# mini-v1_10-smash.net
KiCad netlist of a schematic drawn in EAGLE
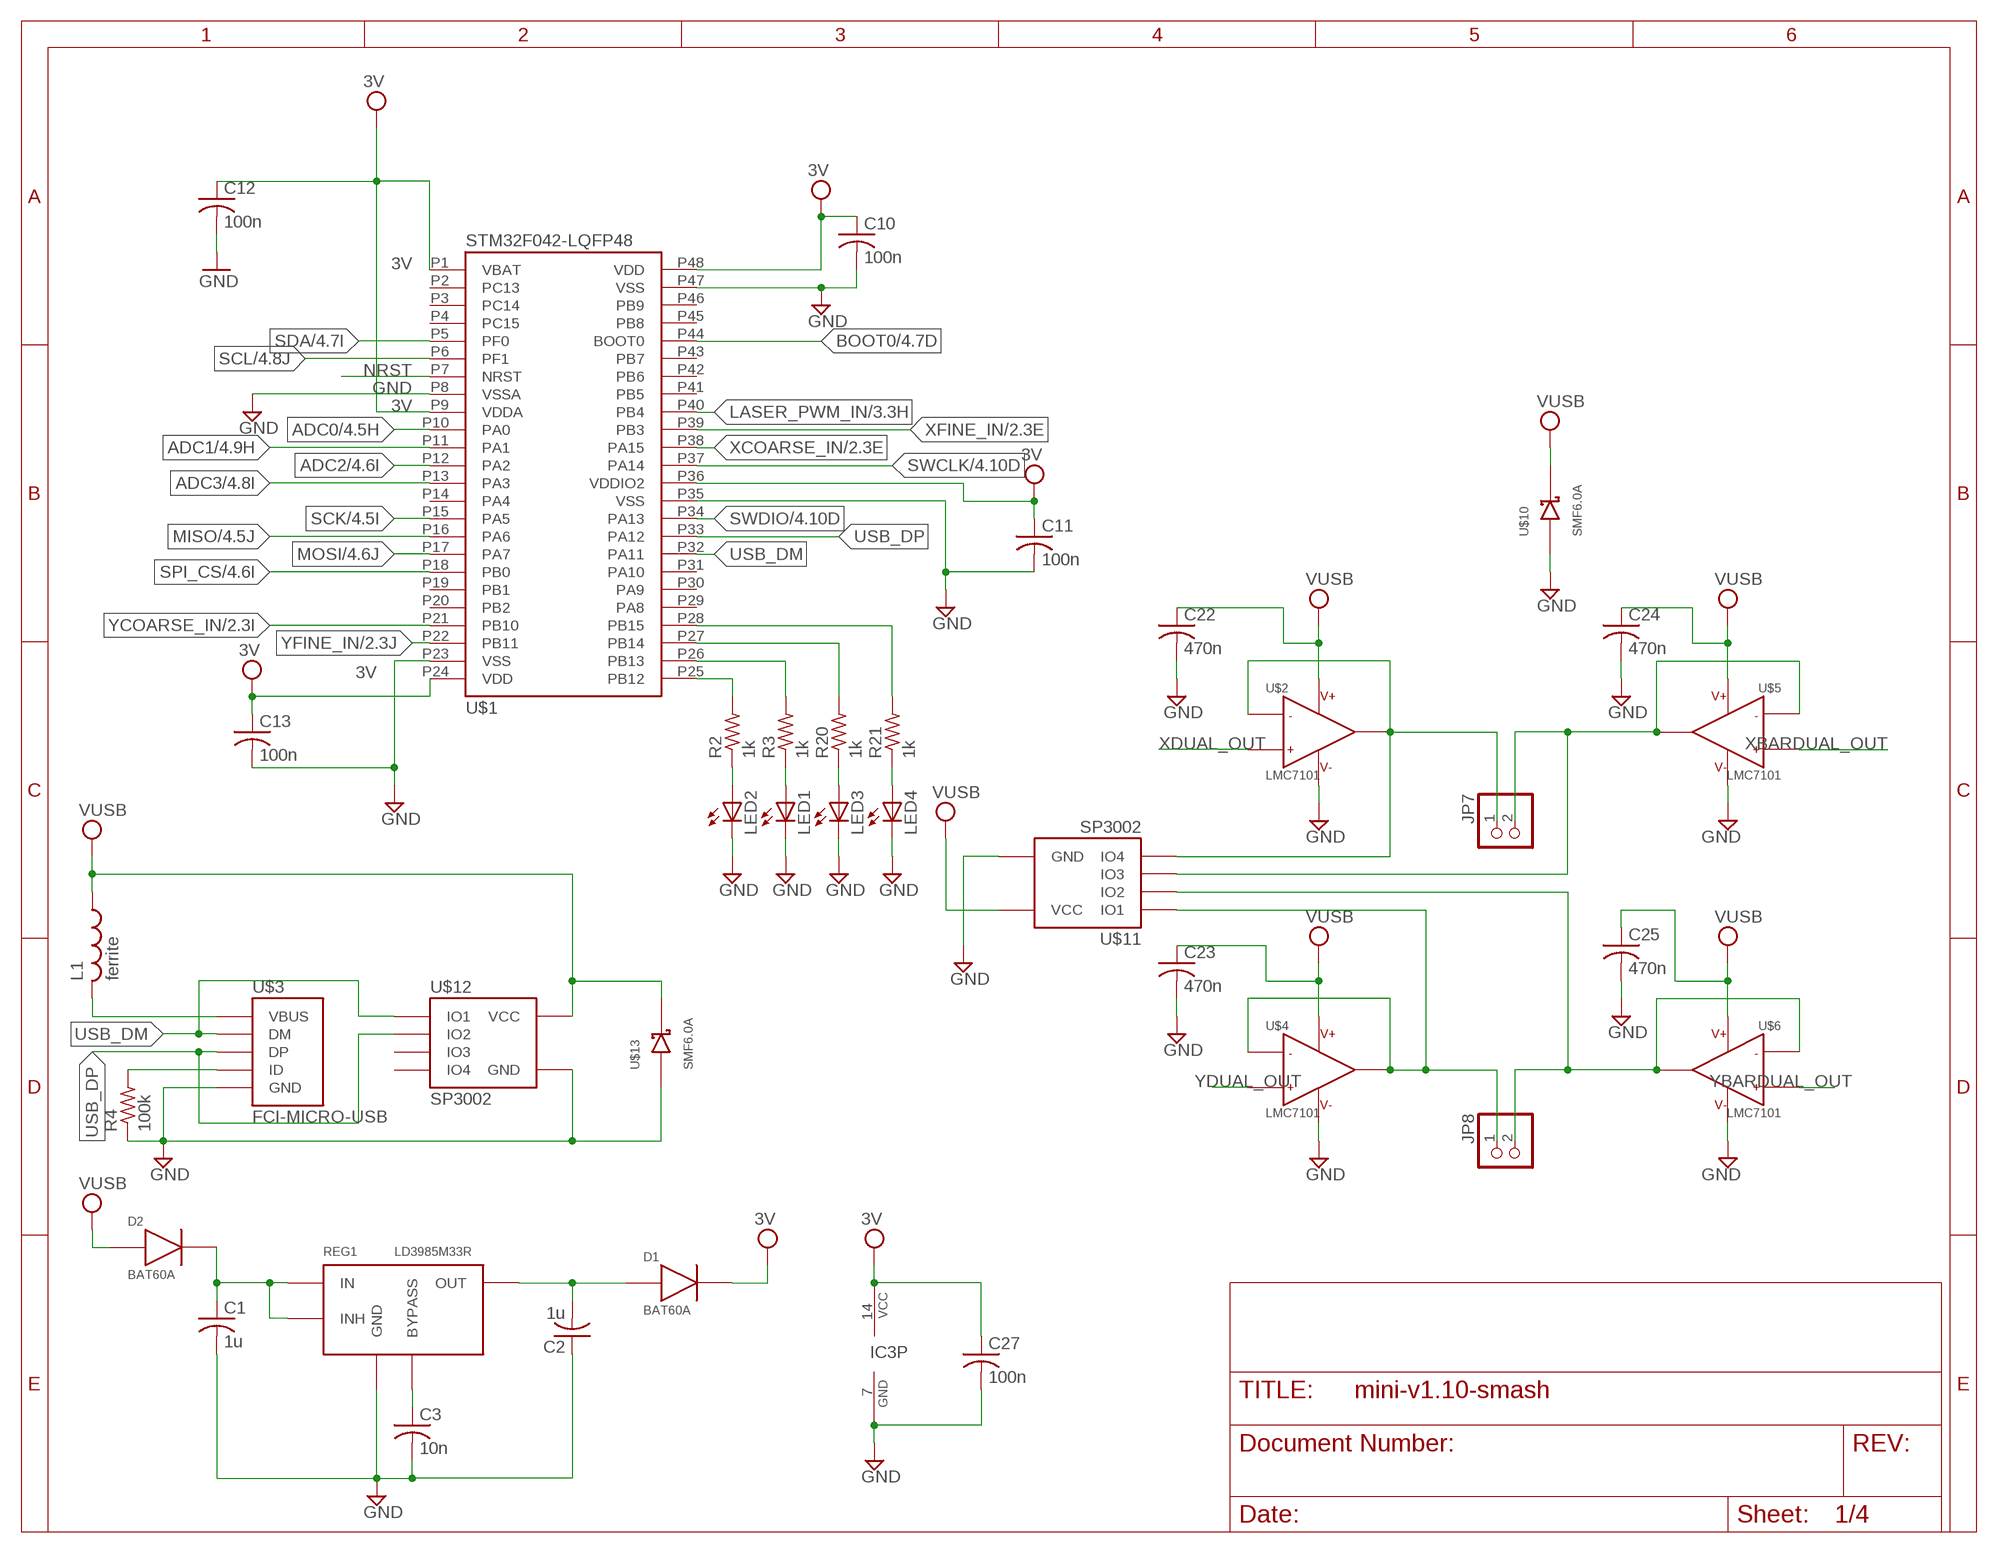
[diagram p0: schematic, sheet 1]
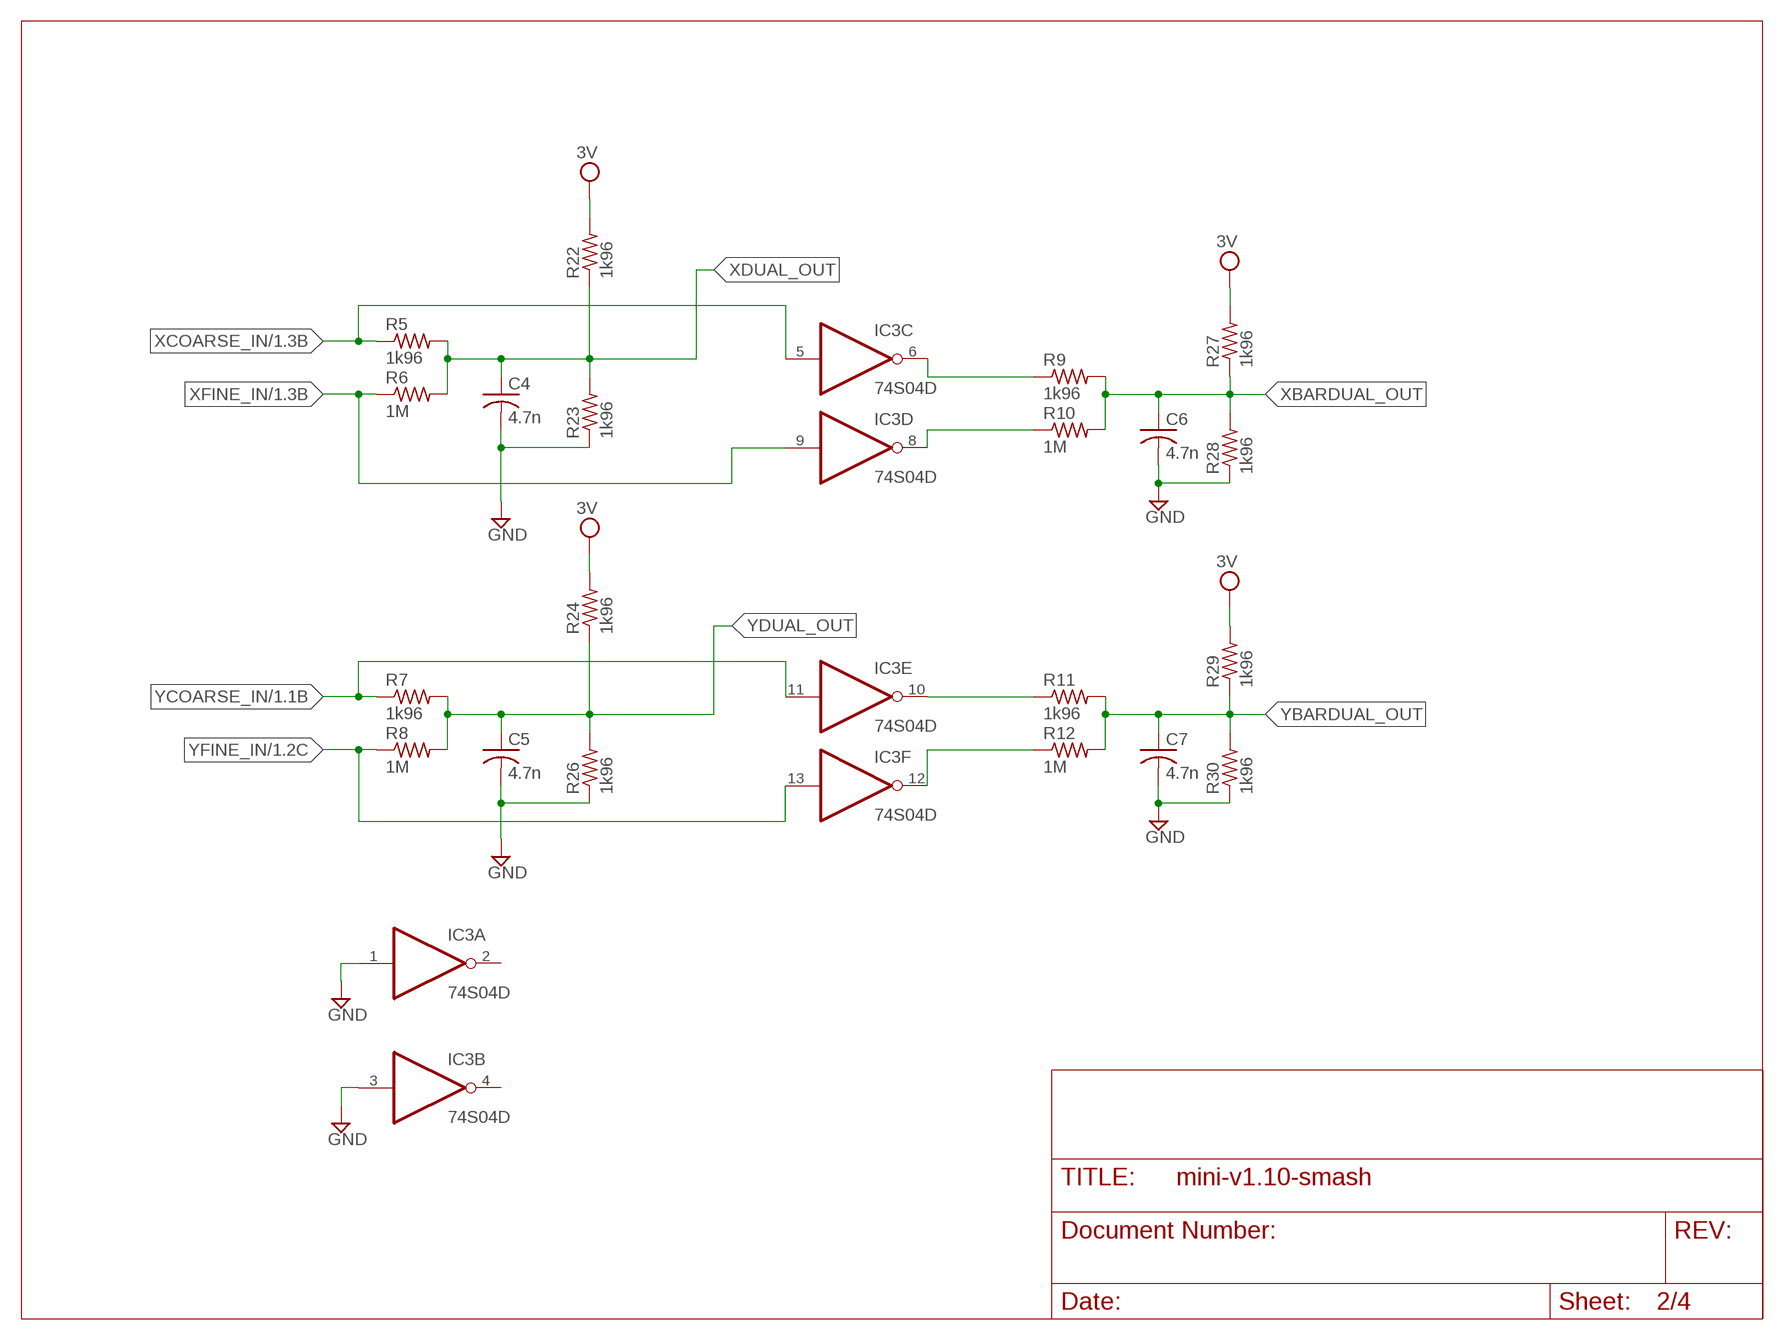
[diagram p1: schematic, sheet 2]
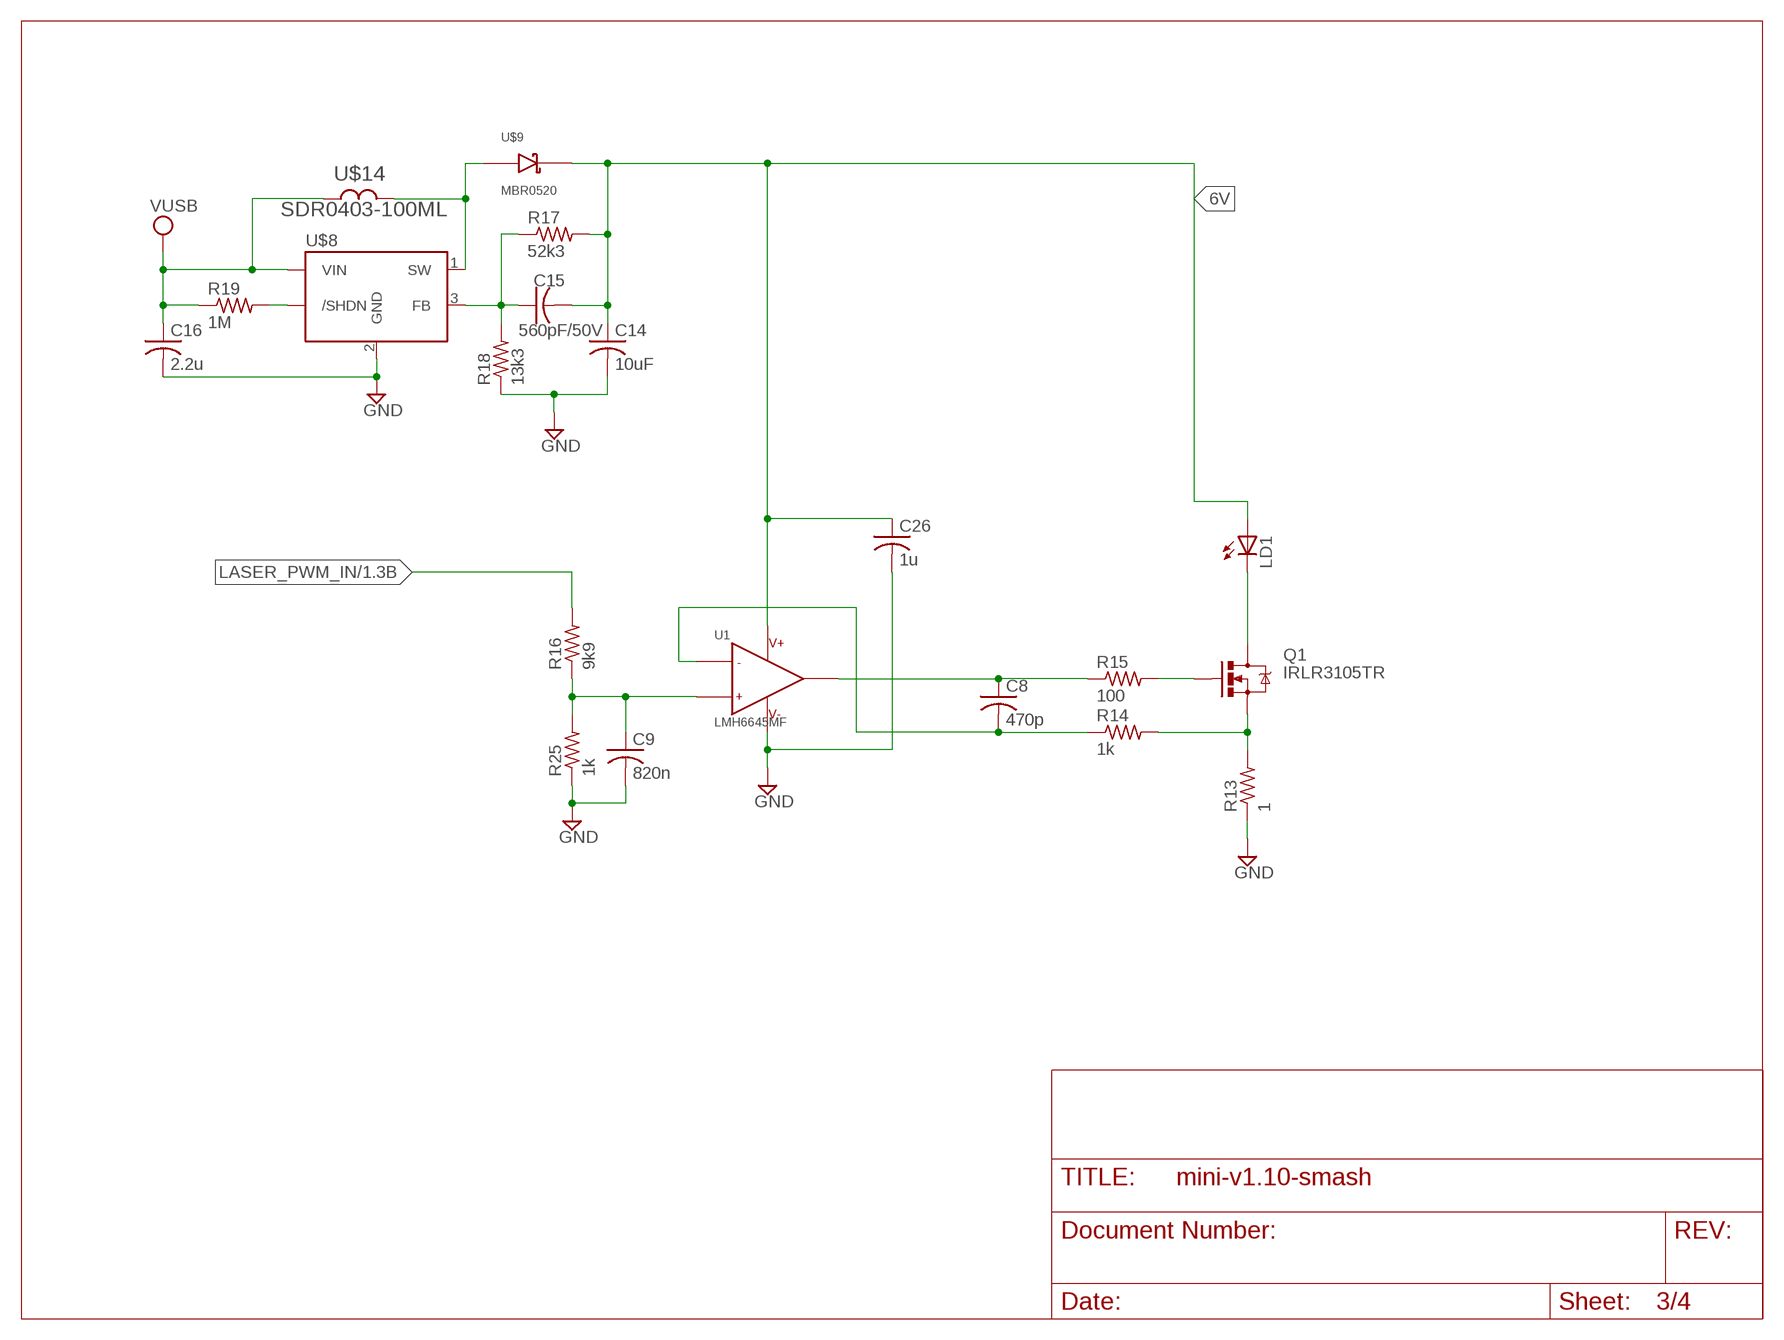
[diagram p2: schematic, sheet 3]
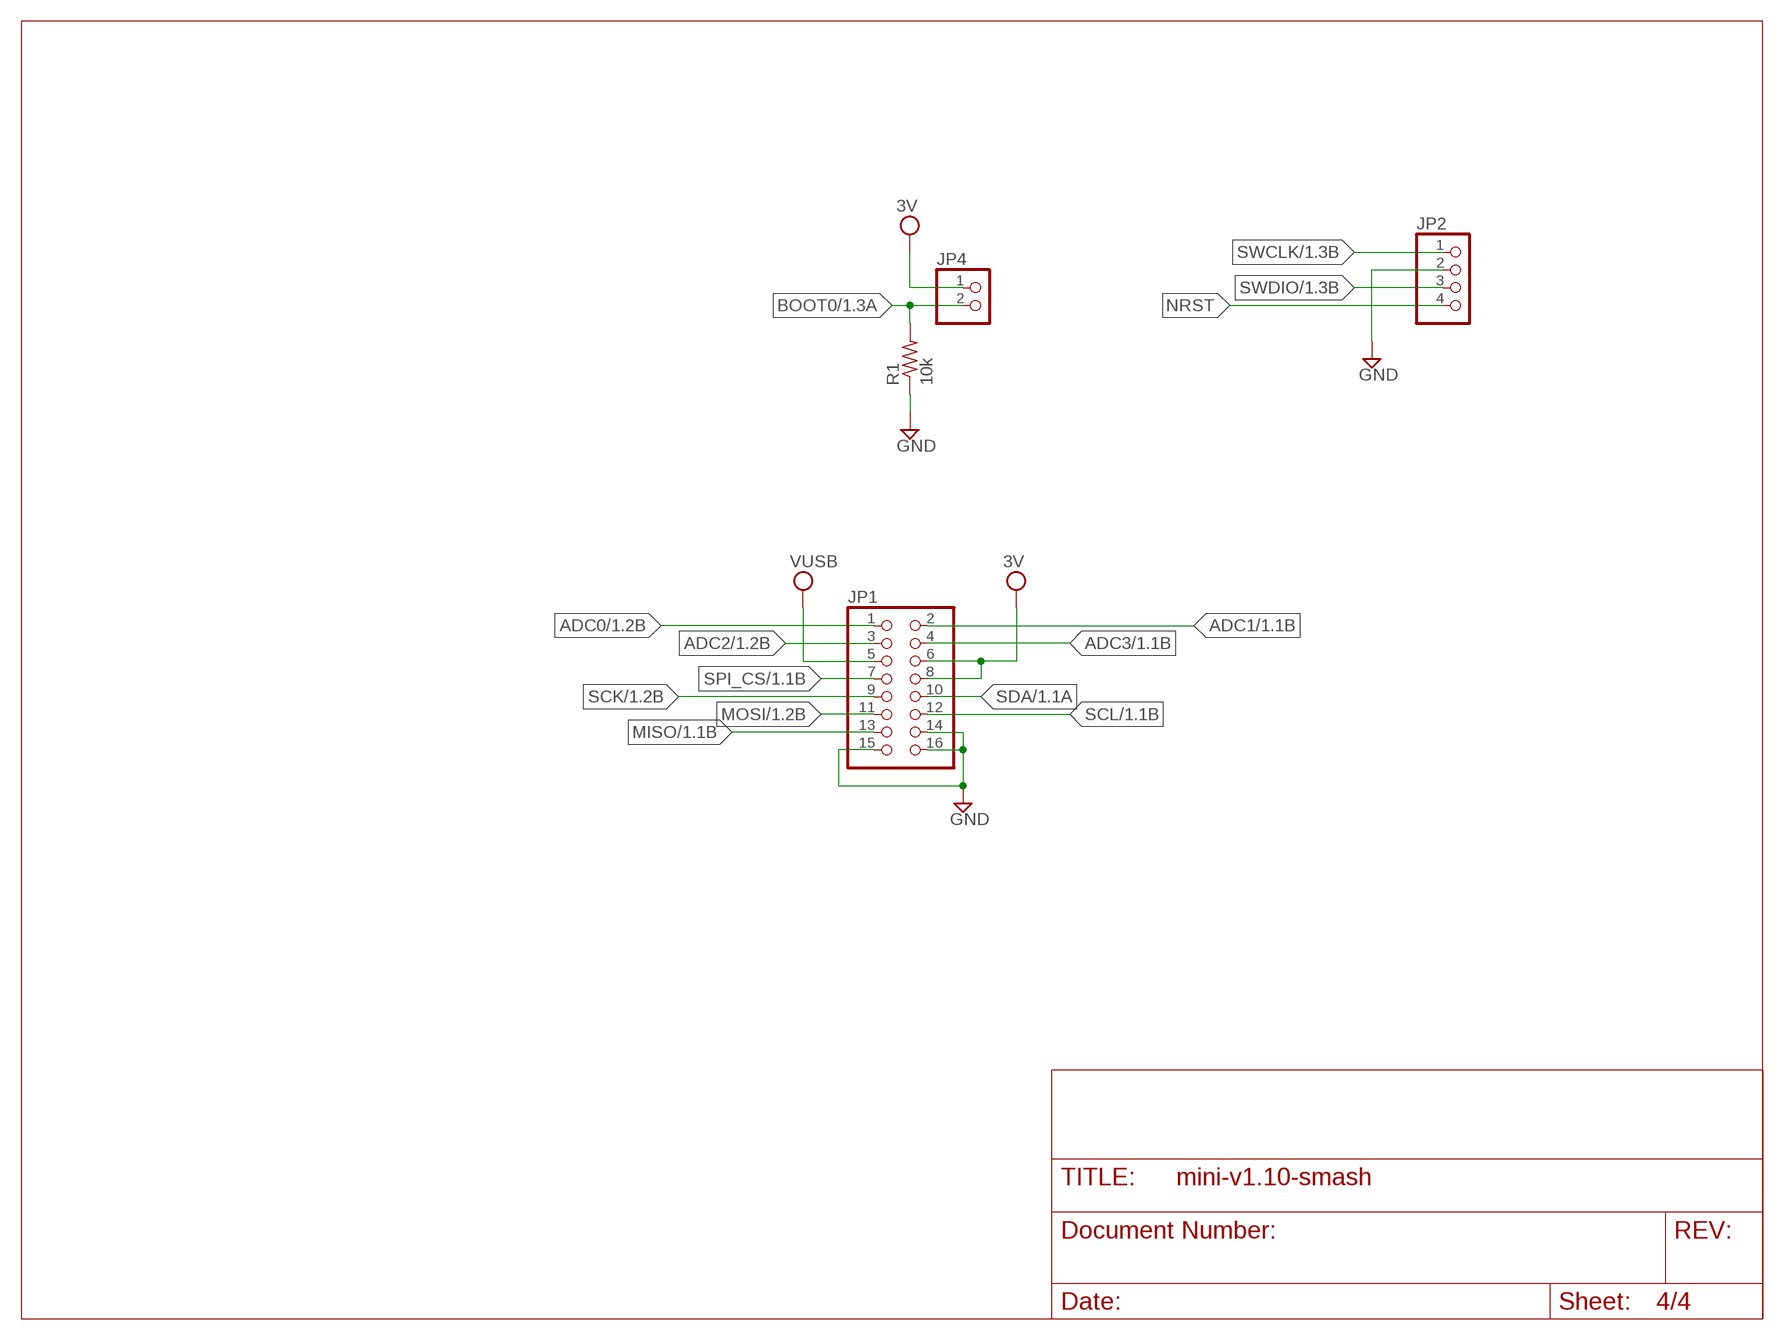
[diagram p3: schematic, sheet 4]

(export (version "E")
  (design (tool "Eeschema 10.0.6"))
  (components
    (comp (ref "C1")
      (value "1u")
      (footprint "eagle-import:C0603")
      (libsource (lib "eagle-import") (part "C-USC0603"))
    )
    (comp (ref "C2")
      (value "1u")
      (footprint "eagle-import:C0603")
      (libsource (lib "eagle-import") (part "C-USC0603"))
    )
    (comp (ref "C3")
      (value "10n")
      (footprint "eagle-import:C0603")
      (libsource (lib "eagle-import") (part "C-USC0603"))
    )
    (comp (ref "C10")
      (value "100n")
      (footprint "eagle-import:C0603")
      (libsource (lib "eagle-import") (part "C-USC0603"))
    )
    (comp (ref "C11")
      (value "100n")
      (footprint "eagle-import:C0603")
      (libsource (lib "eagle-import") (part "C-USC0603"))
    )
    (comp (ref "C12")
      (value "100n")
      (footprint "eagle-import:C0603")
      (libsource (lib "eagle-import") (part "C-USC0603"))
    )
    (comp (ref "C13")
      (value "100n")
      (footprint "eagle-import:C0603")
      (libsource (lib "eagle-import") (part "C-USC0603"))
    )
    (comp (ref "C22")
      (value "470n")
      (footprint "eagle-import:C0603")
      (libsource (lib "eagle-import") (part "C-USC0603"))
    )
    (comp (ref "C23")
      (value "470n")
      (footprint "eagle-import:C0603")
      (libsource (lib "eagle-import") (part "C-USC0603"))
    )
    (comp (ref "C24")
      (value "470n")
      (footprint "eagle-import:C0603")
      (libsource (lib "eagle-import") (part "C-USC0603"))
    )
    (comp (ref "C25")
      (value "470n")
      (footprint "eagle-import:C0603")
      (libsource (lib "eagle-import") (part "C-USC0603"))
    )
    (comp (ref "C27")
      (value "100n")
      (footprint "eagle-import:C0603")
      (libsource (lib "eagle-import") (part "C-USC0603"))
    )
    (comp (ref "D1")
      (value "BAT60A")
      (footprint "eagle-import:SOD323")
      (libsource (lib "eagle-import") (part "BAT60A"))
    )
    (comp (ref "D2")
      (value "BAT60A")
      (footprint "eagle-import:SOD323")
      (libsource (lib "eagle-import") (part "BAT60A"))
    )
    (comp (ref "IC3")
      (value "74S04D")
      (footprint "eagle-import:SO14")
      (libsource (lib "eagle-import") (part "7404DS"))
    )
    (comp (ref "JP7")
      (value "PINHD-1X2")
      (footprint "eagle-import:1X02")
      (libsource (lib "eagle-import") (part "PINHD-1X2"))
    )
    (comp (ref "JP8")
      (value "PINHD-1X2")
      (footprint "eagle-import:1X02")
      (libsource (lib "eagle-import") (part "PINHD-1X2"))
    )
    (comp (ref "L1")
      (value "ferrite")
      (footprint "eagle-import:C0603")
      (libsource (lib "eagle-import") (part "L-US"))
    )
    (comp (ref "LED1")
      (value "LEDCHIP-LED0603")
      (footprint "eagle-import:CHIP-LED0603")
      (libsource (lib "eagle-import") (part "LEDCHIP-LED0603"))
    )
    (comp (ref "LED2")
      (value "LEDCHIP-LED0603")
      (footprint "eagle-import:CHIP-LED0603")
      (libsource (lib "eagle-import") (part "LEDCHIP-LED0603"))
    )
    (comp (ref "LED3")
      (value "LEDCHIP-LED0603")
      (footprint "eagle-import:CHIP-LED0603")
      (libsource (lib "eagle-import") (part "LEDCHIP-LED0603"))
    )
    (comp (ref "LED4")
      (value "LEDCHIP-LED0603")
      (footprint "eagle-import:CHIP-LED0603")
      (libsource (lib "eagle-import") (part "LEDCHIP-LED0603"))
    )
    (comp (ref "R2")
      (value "1k")
      (footprint "eagle-import:R0603")
      (libsource (lib "eagle-import") (part "R-US_R0603"))
    )
    (comp (ref "R3")
      (value "1k")
      (footprint "eagle-import:R0603")
      (libsource (lib "eagle-import") (part "R-US_R0603"))
    )
    (comp (ref "R4")
      (value "100k")
      (footprint "eagle-import:R0603")
      (libsource (lib "eagle-import") (part "R-US_R0603"))
    )
    (comp (ref "R20")
      (value "1k")
      (footprint "eagle-import:R0603")
      (libsource (lib "eagle-import") (part "R-US_R0603"))
    )
    (comp (ref "R21")
      (value "1k")
      (footprint "eagle-import:R0603")
      (libsource (lib "eagle-import") (part "R-US_R0603"))
    )
    (comp (ref "REG1")
      (value "LD3985M33R")
      (footprint "eagle-import:SOT23-5L")
      (libsource (lib "eagle-import") (part "LD3985MXXR"))
    )
    (comp (ref "U$1")
      (value "STM32F042-LQFP48")
      (footprint "eagle-import:LQFP48")
      (libsource (lib "eagle-import") (part "STM32F042-LQFP48"))
    )
    (comp (ref "U$2")
      (value "LMC7101")
      (footprint "eagle-import:SOT23-5")
      (libsource (lib "eagle-import") (part "LMC7101"))
    )
    (comp (ref "U$3")
      (value "FCI-MICRO-USB")
      (footprint "eagle-import:FCI-MICROUSB")
      (libsource (lib "eagle-import") (part "FCI-MICRO-USB"))
    )
    (comp (ref "U$4")
      (value "LMC7101")
      (footprint "eagle-import:SOT23-5")
      (libsource (lib "eagle-import") (part "LMC7101"))
    )
    (comp (ref "U$5")
      (value "LMC7101")
      (footprint "eagle-import:SOT23-5")
      (libsource (lib "eagle-import") (part "LMC7101"))
    )
    (comp (ref "U$6")
      (value "LMC7101")
      (footprint "eagle-import:SOT23-5")
      (libsource (lib "eagle-import") (part "LMC7101"))
    )
    (comp (ref "U$10")
      (value "SMF6.0A")
      (footprint "eagle-import:SOD123")
      (libsource (lib "eagle-import") (part "MBR0520"))
    )
    (comp (ref "U$11")
      (value "SP3002")
      (footprint "eagle-import:SC70-6")
      (libsource (lib "eagle-import") (part "SP3002"))
    )
    (comp (ref "U$12")
      (value "SP3002")
      (footprint "eagle-import:SC70-6")
      (libsource (lib "eagle-import") (part "SP3002"))
    )
    (comp (ref "U$13")
      (value "SMF6.0A")
      (footprint "eagle-import:SOD123")
      (libsource (lib "eagle-import") (part "MBR0520"))
    )
    (comp (ref "C8")
      (value "470p")
      (footprint "eagle-import:C0603")
      (libsource (lib "eagle-import") (part "C-USC0603"))
    )
    (comp (ref "C9")
      (value "820n")
      (footprint "eagle-import:C0603")
      (libsource (lib "eagle-import") (part "C-USC0603"))
    )
    (comp (ref "C14")
      (value "10uF")
      (footprint "eagle-import:C0603")
      (libsource (lib "eagle-import") (part "C-USC0603"))
    )
    (comp (ref "C15")
      (value "560pF/50V")
      (footprint "eagle-import:C0603")
      (libsource (lib "eagle-import") (part "C-USC0603"))
    )
    (comp (ref "C16")
      (value "2.2u")
      (footprint "eagle-import:C0603")
      (libsource (lib "eagle-import") (part "C-USC0603"))
    )
    (comp (ref "C26")
      (value "1u")
      (footprint "eagle-import:C0603")
      (libsource (lib "eagle-import") (part "C-USC0603"))
    )
    (comp (ref "LD1")
      (value "LASERDIODELD2")
      (footprint "eagle-import:LASERDIODE2")
      (fields (field (name "MPN") "3 x (0552-2-15-15-11-27-10-0)"))
      (libsource (lib "eagle-import") (part "LASERDIODELD2"))
    )
    (comp (ref "Q1")
      (value "IRLR3105TR")
      (footprint "eagle-import:DPAK")
      (libsource (lib "eagle-import") (part "FET-N-IRLR3105TRIRLR3105TR"))
    )
    (comp (ref "R13")
      (value "1")
      (footprint "eagle-import:R0603")
      (libsource (lib "eagle-import") (part "R-US_R0603"))
    )
    (comp (ref "R14")
      (value "1k")
      (footprint "eagle-import:R0603")
      (libsource (lib "eagle-import") (part "R-US_R0603"))
    )
    (comp (ref "R15")
      (value "100")
      (footprint "eagle-import:R0603")
      (libsource (lib "eagle-import") (part "R-US_R0603"))
    )
    (comp (ref "R16")
      (value "9k9")
      (footprint "eagle-import:R0603")
      (libsource (lib "eagle-import") (part "R-US_R0603"))
    )
    (comp (ref "R17")
      (value "52k3")
      (footprint "eagle-import:R0603")
      (libsource (lib "eagle-import") (part "R-US_R0603"))
    )
    (comp (ref "R18")
      (value "13k3")
      (footprint "eagle-import:R0603")
      (libsource (lib "eagle-import") (part "R-US_R0603"))
    )
    (comp (ref "R19")
      (value "1M")
      (footprint "eagle-import:R0603")
      (libsource (lib "eagle-import") (part "R-US_R0603"))
    )
    (comp (ref "R25")
      (value "1k")
      (footprint "eagle-import:R0603")
      (libsource (lib "eagle-import") (part "R-US_R0603"))
    )
    (comp (ref "U$8")
      (value "LMR62014")
      (footprint "eagle-import:SOT23-5")
      (libsource (lib "eagle-import") (part "LMR62014"))
    )
    (comp (ref "U$9")
      (value "MBR0520")
      (footprint "eagle-import:SOD123")
      (libsource (lib "eagle-import") (part "MBR0520"))
    )
    (comp (ref "U$14")
      (value "SDR0403-100ML")
      (footprint "eagle-import:SDR0403")
      (libsource (lib "eagle-import") (part "SDR0403"))
    )
    (comp (ref "U1")
      (value "LMH6645MF")
      (footprint "eagle-import:SOT23-5")
      (libsource (lib "eagle-import") (part "OPAMP-SINGLELMH6645MF"))
    )
    (comp (ref "C4")
      (value "4.7n")
      (footprint "eagle-import:C0603")
      (libsource (lib "eagle-import") (part "C-USC0603"))
    )
    (comp (ref "C5")
      (value "4.7n")
      (footprint "eagle-import:C0603")
      (libsource (lib "eagle-import") (part "C-USC0603"))
    )
    (comp (ref "C6")
      (value "4.7n")
      (footprint "eagle-import:C0603")
      (libsource (lib "eagle-import") (part "C-USC0603"))
    )
    (comp (ref "C7")
      (value "4.7n")
      (footprint "eagle-import:C0603")
      (libsource (lib "eagle-import") (part "C-USC0603"))
    )
    (comp (ref "R5")
      (value "1k96")
      (footprint "eagle-import:R0603")
      (libsource (lib "eagle-import") (part "R-US_R0603"))
    )
    (comp (ref "R6")
      (value "1M")
      (footprint "eagle-import:R0603")
      (libsource (lib "eagle-import") (part "R-US_R0603"))
    )
    (comp (ref "R7")
      (value "1k96")
      (footprint "eagle-import:R0603")
      (libsource (lib "eagle-import") (part "R-US_R0603"))
    )
    (comp (ref "R8")
      (value "1M")
      (footprint "eagle-import:R0603")
      (libsource (lib "eagle-import") (part "R-US_R0603"))
    )
    (comp (ref "R9")
      (value "1k96")
      (footprint "eagle-import:R0603")
      (libsource (lib "eagle-import") (part "R-US_R0603"))
    )
    (comp (ref "R10")
      (value "1M")
      (footprint "eagle-import:R0603")
      (libsource (lib "eagle-import") (part "R-US_R0603"))
    )
    (comp (ref "R11")
      (value "1k96")
      (footprint "eagle-import:R0603")
      (libsource (lib "eagle-import") (part "R-US_R0603"))
    )
    (comp (ref "R12")
      (value "1M")
      (footprint "eagle-import:R0603")
      (libsource (lib "eagle-import") (part "R-US_R0603"))
    )
    (comp (ref "R22")
      (value "1k96")
      (footprint "eagle-import:R0603")
      (libsource (lib "eagle-import") (part "R-US_R0603"))
    )
    (comp (ref "R23")
      (value "1k96")
      (footprint "eagle-import:R0603")
      (libsource (lib "eagle-import") (part "R-US_R0603"))
    )
    (comp (ref "R24")
      (value "1k96")
      (footprint "eagle-import:R0603")
      (libsource (lib "eagle-import") (part "R-US_R0603"))
    )
    (comp (ref "R26")
      (value "1k96")
      (footprint "eagle-import:R0603")
      (libsource (lib "eagle-import") (part "R-US_R0603"))
    )
    (comp (ref "R27")
      (value "1k96")
      (footprint "eagle-import:R0603")
      (libsource (lib "eagle-import") (part "R-US_R0603"))
    )
    (comp (ref "R28")
      (value "1k96")
      (footprint "eagle-import:R0603")
      (libsource (lib "eagle-import") (part "R-US_R0603"))
    )
    (comp (ref "R29")
      (value "1k96")
      (footprint "eagle-import:R0603")
      (libsource (lib "eagle-import") (part "R-US_R0603"))
    )
    (comp (ref "R30")
      (value "1k96")
      (footprint "eagle-import:R0603")
      (libsource (lib "eagle-import") (part "R-US_R0603"))
    )
    (comp (ref "JP1")
      (value "PINHD-2X8")
      (footprint "eagle-import:2X08")
      (libsource (lib "eagle-import") (part "PINHD-2X8"))
    )
    (comp (ref "JP2")
      (value "PINHD-1X4")
      (footprint "eagle-import:1X04")
      (libsource (lib "eagle-import") (part "PINHD-1X4"))
    )
    (comp (ref "JP4")
      (value "PINHD-1X2")
      (footprint "eagle-import:1X02")
      (libsource (lib "eagle-import") (part "PINHD-1X2"))
    )
    (comp (ref "R1")
      (value "10k")
      (footprint "eagle-import:R0603")
      (libsource (lib "eagle-import") (part "R-US_R0603"))
    )
  )
  (nets
    (net (code "1") (name "3V") (class "Default")
      (node (ref "C10") (pin "1") (pinfunction "1_1") (pintype "passive"))
      (node (ref "C11") (pin "1") (pinfunction "1_1") (pintype "passive"))
      (node (ref "C12") (pin "1") (pinfunction "1_1") (pintype "passive"))
      (node (ref "C13") (pin "1") (pinfunction "1_1") (pintype "passive"))
      (node (ref "C27") (pin "1") (pinfunction "1_1") (pintype "passive"))
      (node (ref "D1") (pin "1") (pinfunction "1_1") (pintype "bidirectional"))
      (node (ref "IC3") (pin "14") (pinfunction "VCC_14") (pintype "power_in"))
      (node (ref "JP1") (pin "6") (pinfunction "6_6") (pintype "passive"))
      (node (ref "JP1") (pin "8") (pinfunction "8_8") (pintype "passive"))
      (node (ref "JP4") (pin "1") (pinfunction "1_1") (pintype "passive"))
      (node (ref "R22") (pin "2") (pinfunction "2_2") (pintype "passive"))
      (node (ref "R24") (pin "2") (pinfunction "2_2") (pintype "passive"))
      (node (ref "R27") (pin "2") (pinfunction "2_2") (pintype "passive"))
      (node (ref "R29") (pin "2") (pinfunction "2_2") (pintype "passive"))
      (node (ref "U$1") (pin "P1") (pinfunction "VBAT_P1") (pintype "bidirectional"))
      (node (ref "U$1") (pin "P24") (pinfunction "VDD_P24") (pintype "bidirectional"))
      (node (ref "U$1") (pin "P36") (pinfunction "VDDIO2_P36") (pintype "bidirectional"))
      (node (ref "U$1") (pin "P48") (pinfunction "VDD_P48") (pintype "bidirectional"))
      (node (ref "U$1") (pin "P9") (pinfunction "VDDA_P9") (pintype "bidirectional"))
    )
    (net (code "2") (name "6V") (class "Default")
      (node (ref "C14") (pin "1") (pinfunction "1_1") (pintype "passive"))
      (node (ref "C15") (pin "2") (pinfunction "2_2") (pintype "passive"))
      (node (ref "C26") (pin "1") (pinfunction "1_1") (pintype "passive"))
      (node (ref "LD1") (pin "P$1") (pinfunction "A_P$1") (pintype "passive"))
      (node (ref "R17") (pin "2") (pinfunction "2_2") (pintype "passive"))
      (node (ref "U$9") (pin "CATHODE") (pinfunction "CATHODE_CATHODE") (pintype "bidirectional"))
      (node (ref "U1") (pin "5") (pinfunction "V+_5") (pintype "power_in"))
    )
    (net (code "3") (name "ADC0") (class "Default")
      (node (ref "JP1") (pin "1") (pinfunction "1_1") (pintype "passive"))
      (node (ref "U$1") (pin "P10") (pinfunction "PA0_P10") (pintype "bidirectional"))
    )
    (net (code "4") (name "ADC1") (class "Default")
      (node (ref "JP1") (pin "2") (pinfunction "2_2") (pintype "passive"))
      (node (ref "U$1") (pin "P11") (pinfunction "PA1_P11") (pintype "bidirectional"))
    )
    (net (code "5") (name "ADC2") (class "Default")
      (node (ref "JP1") (pin "3") (pinfunction "3_3") (pintype "passive"))
      (node (ref "U$1") (pin "P12") (pinfunction "PA2_P12") (pintype "bidirectional"))
    )
    (net (code "6") (name "ADC3") (class "Default")
      (node (ref "JP1") (pin "4") (pinfunction "4_4") (pintype "passive"))
      (node (ref "U$1") (pin "P13") (pinfunction "PA3_P13") (pintype "bidirectional"))
    )
    (net (code "7") (name "BOOT0") (class "Default")
      (node (ref "JP4") (pin "2") (pinfunction "2_2") (pintype "passive"))
      (node (ref "R1") (pin "2") (pinfunction "2_2") (pintype "passive"))
      (node (ref "U$1") (pin "P44") (pinfunction "BOOT0_P44") (pintype "bidirectional"))
    )
    (net (code "8") (name "GND") (class "Default")
      (node (ref "C1") (pin "2") (pinfunction "2_2") (pintype "passive"))
      (node (ref "C10") (pin "2") (pinfunction "2_2") (pintype "passive"))
      (node (ref "C11") (pin "2") (pinfunction "2_2") (pintype "passive"))
      (node (ref "C12") (pin "2") (pinfunction "2_2") (pintype "passive"))
      (node (ref "C13") (pin "2") (pinfunction "2_2") (pintype "passive"))
      (node (ref "C14") (pin "2") (pinfunction "2_2") (pintype "passive"))
      (node (ref "C16") (pin "2") (pinfunction "2_2") (pintype "passive"))
      (node (ref "C2") (pin "1") (pinfunction "1_1") (pintype "passive"))
      (node (ref "C22") (pin "2") (pinfunction "2_2") (pintype "passive"))
      (node (ref "C23") (pin "2") (pinfunction "2_2") (pintype "passive"))
      (node (ref "C24") (pin "2") (pinfunction "2_2") (pintype "passive"))
      (node (ref "C25") (pin "2") (pinfunction "2_2") (pintype "passive"))
      (node (ref "C26") (pin "2") (pinfunction "2_2") (pintype "passive"))
      (node (ref "C27") (pin "2") (pinfunction "2_2") (pintype "passive"))
      (node (ref "C3") (pin "2") (pinfunction "2_2") (pintype "passive"))
      (node (ref "C4") (pin "2") (pinfunction "2_2") (pintype "passive"))
      (node (ref "C5") (pin "2") (pinfunction "2_2") (pintype "passive"))
      (node (ref "C6") (pin "2") (pinfunction "2_2") (pintype "passive"))
      (node (ref "C7") (pin "2") (pinfunction "2_2") (pintype "passive"))
      (node (ref "C9") (pin "2") (pinfunction "2_2") (pintype "passive"))
      (node (ref "IC3") (pin "1") (pinfunction "I_1") (pintype "input"))
      (node (ref "IC3") (pin "3") (pinfunction "I_3") (pintype "input"))
      (node (ref "IC3") (pin "7") (pinfunction "GND_7") (pintype "power_in"))
      (node (ref "JP1") (pin "14") (pinfunction "14_14") (pintype "passive"))
      (node (ref "JP1") (pin "15") (pinfunction "15_15") (pintype "passive"))
      (node (ref "JP1") (pin "16") (pinfunction "16_16") (pintype "passive"))
      (node (ref "JP2") (pin "2") (pinfunction "2_2") (pintype "passive"))
      (node (ref "LED1") (pin "C") (pinfunction "C_C") (pintype "passive"))
      (node (ref "LED2") (pin "C") (pinfunction "C_C") (pintype "passive"))
      (node (ref "LED3") (pin "C") (pinfunction "C_C") (pintype "passive"))
      (node (ref "LED4") (pin "C") (pinfunction "C_C") (pintype "passive"))
      (node (ref "R1") (pin "1") (pinfunction "1_1") (pintype "passive"))
      (node (ref "R13") (pin "1") (pinfunction "1_1") (pintype "passive"))
      (node (ref "R18") (pin "1") (pinfunction "1_1") (pintype "passive"))
      (node (ref "R23") (pin "1") (pinfunction "1_1") (pintype "passive"))
      (node (ref "R25") (pin "1") (pinfunction "1_1") (pintype "passive"))
      (node (ref "R26") (pin "1") (pinfunction "1_1") (pintype "passive"))
      (node (ref "R28") (pin "1") (pinfunction "1_1") (pintype "passive"))
      (node (ref "R30") (pin "1") (pinfunction "1_1") (pintype "passive"))
      (node (ref "R4") (pin "1") (pinfunction "1_1") (pintype "passive"))
      (node (ref "REG1") (pin "GND") (pinfunction "GND_GND") (pintype "bidirectional"))
      (node (ref "U$1") (pin "P23") (pinfunction "VSS_P23") (pintype "bidirectional"))
      (node (ref "U$1") (pin "P35") (pinfunction "VSS_P35") (pintype "bidirectional"))
      (node (ref "U$1") (pin "P47") (pinfunction "VSS_P47") (pintype "bidirectional"))
      (node (ref "U$1") (pin "P8") (pinfunction "VSSA_P8") (pintype "bidirectional"))
      (node (ref "U$10") (pin "ANODE") (pinfunction "ANODE_ANODE") (pintype "bidirectional"))
      (node (ref "U$11") (pin "P2") (pinfunction "GND_P2") (pintype "power_in"))
      (node (ref "U$12") (pin "P2") (pinfunction "GND_P2") (pintype "power_in"))
      (node (ref "U$13") (pin "ANODE") (pinfunction "ANODE_ANODE") (pintype "bidirectional"))
      (node (ref "U$2") (pin "5") (pinfunction "P5_5") (pintype "power_in"))
      (node (ref "U$3") (pin "P5") (pinfunction "GND_P5") (pintype "bidirectional"))
      (node (ref "U$4") (pin "5") (pinfunction "P5_5") (pintype "power_in"))
      (node (ref "U$5") (pin "5") (pinfunction "P5_5") (pintype "power_in"))
      (node (ref "U$6") (pin "5") (pinfunction "P5_5") (pintype "power_in"))
      (node (ref "U$8") (pin "2") (pinfunction "GND_2") (pintype "bidirectional"))
      (node (ref "U1") (pin "2") (pinfunction "V-_2") (pintype "power_in"))
    )
    (net (code "9") (name "LASER_PWM_IN") (class "Default")
      (node (ref "R16") (pin "2") (pinfunction "2_2") (pintype "passive"))
      (node (ref "U$1") (pin "P40") (pinfunction "PB4_P40") (pintype "bidirectional"))
    )
    (net (code "10") (name "MISO") (class "Default")
      (node (ref "JP1") (pin "13") (pinfunction "13_13") (pintype "passive"))
      (node (ref "U$1") (pin "P16") (pinfunction "PA6_P16") (pintype "bidirectional"))
    )
    (net (code "11") (name "MOSI") (class "Default")
      (node (ref "JP1") (pin "11") (pinfunction "11_11") (pintype "passive"))
      (node (ref "U$1") (pin "P17") (pinfunction "PA7_P17") (pintype "bidirectional"))
    )
    (net (code "12") (name "NRST") (class "Default")
      (node (ref "JP2") (pin "4") (pinfunction "4_4") (pintype "passive"))
      (node (ref "U$1") (pin "P7") (pinfunction "NRST_P7") (pintype "bidirectional"))
    )
    (net (code "13") (name "Net-(C2-Pad2)") (class "Default")
      (node (ref "C2") (pin "2") (pinfunction "2_2") (pintype "passive"))
      (node (ref "D1") (pin "2") (pinfunction "2_2") (pintype "bidirectional"))
      (node (ref "REG1") (pin "OUT") (pinfunction "OUT_OUT") (pintype "bidirectional"))
    )
    (net (code "14") (name "Net-(C3-Pad1)") (class "Default")
      (node (ref "C3") (pin "1") (pinfunction "1_1") (pintype "passive"))
      (node (ref "REG1") (pin "BYPASS") (pinfunction "BYPASS_BYPASS") (pintype "bidirectional"))
    )
    (net (code "15") (name "Net-(IC3C-O)") (class "Default")
      (node (ref "IC3") (pin "6") (pinfunction "O_6") (pintype "output"))
      (node (ref "R9") (pin "1") (pinfunction "1_1") (pintype "passive"))
    )
    (net (code "16") (name "Net-(IC3D-O)") (class "Default")
      (node (ref "IC3") (pin "8") (pinfunction "O_8") (pintype "output"))
      (node (ref "R10") (pin "1") (pinfunction "1_1") (pintype "passive"))
    )
    (net (code "17") (name "Net-(IC3E-O)") (class "Default")
      (node (ref "IC3") (pin "10") (pinfunction "O_10") (pintype "output"))
      (node (ref "R11") (pin "1") (pinfunction "1_1") (pintype "passive"))
    )
    (net (code "18") (name "Net-(IC3F-O)") (class "Default")
      (node (ref "IC3") (pin "12") (pinfunction "O_12") (pintype "output"))
      (node (ref "R12") (pin "1") (pinfunction "1_1") (pintype "passive"))
    )
    (net (code "19") (name "Net-(LD1-C)") (class "Default")
      (node (ref "LD1") (pin "P$3") (pinfunction "C_P$3") (pintype "passive"))
      (node (ref "Q1") (pin "4") (pinfunction "D_4") (pintype "passive"))
    )
    (net (code "20") (name "Net-(LED1-PadA)") (class "Default")
      (node (ref "LED1") (pin "A") (pinfunction "A_A") (pintype "passive"))
      (node (ref "R3") (pin "1") (pinfunction "1_1") (pintype "passive"))
    )
    (net (code "21") (name "Net-(LED2-PadA)") (class "Default")
      (node (ref "LED2") (pin "A") (pinfunction "A_A") (pintype "passive"))
      (node (ref "R2") (pin "1") (pinfunction "1_1") (pintype "passive"))
    )
    (net (code "22") (name "Net-(LED3-PadA)") (class "Default")
      (node (ref "LED3") (pin "A") (pinfunction "A_A") (pintype "passive"))
      (node (ref "R20") (pin "1") (pinfunction "1_1") (pintype "passive"))
    )
    (net (code "23") (name "Net-(LED4-PadA)") (class "Default")
      (node (ref "LED4") (pin "A") (pinfunction "A_A") (pintype "passive"))
      (node (ref "R21") (pin "1") (pinfunction "1_1") (pintype "passive"))
    )
    (net (code "24") (name "Net-(Q1-G)") (class "Default")
      (node (ref "Q1") (pin "1") (pinfunction "G_1") (pintype "passive"))
      (node (ref "R15") (pin "2") (pinfunction "2_2") (pintype "passive"))
    )
    (net (code "25") (name "Net-(Q1-S)") (class "Default")
      (node (ref "Q1") (pin "3") (pinfunction "S_3") (pintype "passive"))
      (node (ref "R13") (pin "2") (pinfunction "2_2") (pintype "passive"))
      (node (ref "R14") (pin "2") (pinfunction "2_2") (pintype "passive"))
    )
    (net (code "26") (name "Net-(REG1-INH)") (class "Default")
      (node (ref "C1") (pin "1") (pinfunction "1_1") (pintype "passive"))
      (node (ref "D2") (pin "1") (pinfunction "1_1") (pintype "bidirectional"))
      (node (ref "REG1") (pin "IN") (pinfunction "IN_IN") (pintype "bidirectional"))
      (node (ref "REG1") (pin "INHIBIT") (pinfunction "INH_INHIBIT") (pintype "bidirectional"))
    )
    (net (code "27") (name "Net-(U$1-PB12)") (class "Default")
      (node (ref "R2") (pin "2") (pinfunction "2_2") (pintype "passive"))
      (node (ref "U$1") (pin "P25") (pinfunction "PB12_P25") (pintype "bidirectional"))
    )
    (net (code "28") (name "Net-(U$1-PB13)") (class "Default")
      (node (ref "R3") (pin "2") (pinfunction "2_2") (pintype "passive"))
      (node (ref "U$1") (pin "P26") (pinfunction "PB13_P26") (pintype "bidirectional"))
    )
    (net (code "29") (name "Net-(U$1-PB14)") (class "Default")
      (node (ref "R20") (pin "2") (pinfunction "2_2") (pintype "passive"))
      (node (ref "U$1") (pin "P27") (pinfunction "PB14_P27") (pintype "bidirectional"))
    )
    (net (code "30") (name "Net-(U$1-PB15)") (class "Default")
      (node (ref "R21") (pin "2") (pinfunction "2_2") (pintype "passive"))
      (node (ref "U$1") (pin "P28") (pinfunction "PB15_P28") (pintype "bidirectional"))
    )
    (net (code "31") (name "Net-(U$3-ID)") (class "Default")
      (node (ref "R4") (pin "2") (pinfunction "2_2") (pintype "passive"))
      (node (ref "U$3") (pin "P4") (pinfunction "ID_P4") (pintype "bidirectional"))
    )
    (net (code "32") (name "Net-(U$3-VBUS)") (class "Default")
      (node (ref "L1") (pin "2") (pinfunction "2_2") (pintype "passive"))
      (node (ref "U$3") (pin "P1") (pinfunction "VBUS_P1") (pintype "bidirectional"))
    )
    (net (code "33") (name "Net-(U$8-FB)") (class "Default")
      (node (ref "C15") (pin "1") (pinfunction "1_1") (pintype "passive"))
      (node (ref "R17") (pin "1") (pinfunction "1_1") (pintype "passive"))
      (node (ref "R18") (pin "2") (pinfunction "2_2") (pintype "passive"))
      (node (ref "U$8") (pin "3") (pinfunction "FB_3") (pintype "bidirectional"))
    )
    (net (code "34") (name "Net-(U$8-SW)") (class "Default")
      (node (ref "U$14") (pin "P$2") (pinfunction "P$2_P$2") (pintype "bidirectional"))
      (node (ref "U$8") (pin "1") (pinfunction "SW_1") (pintype "bidirectional"))
      (node (ref "U$9") (pin "ANODE") (pinfunction "ANODE_ANODE") (pintype "bidirectional"))
    )
    (net (code "35") (name "Net-(U$8-{slash}SHDN)") (class "Default")
      (node (ref "R19") (pin "2") (pinfunction "2_2") (pintype "passive"))
      (node (ref "U$8") (pin "4") (pinfunction "/SHDN_4") (pintype "bidirectional"))
    )
    (net (code "36") (name "Net-(U$11-IO1)") (class "Default")
      (node (ref "JP8") (pin "1") (pinfunction "1_1") (pintype "passive"))
      (node (ref "U$11") (pin "P1") (pinfunction "IO1_P1") (pintype "bidirectional"))
      (node (ref "U$4") (pin "1") (pinfunction "P1_1") (pintype "bidirectional"))
      (node (ref "U$4") (pin "4") (pinfunction "P4_4") (pintype "bidirectional"))
    )
    (net (code "37") (name "Net-(U$11-IO2)") (class "Default")
      (node (ref "JP8") (pin "2") (pinfunction "2_2") (pintype "passive"))
      (node (ref "U$11") (pin "P3") (pinfunction "IO2_P3") (pintype "bidirectional"))
      (node (ref "U$6") (pin "1") (pinfunction "P1_1") (pintype "bidirectional"))
      (node (ref "U$6") (pin "4") (pinfunction "P4_4") (pintype "bidirectional"))
    )
    (net (code "38") (name "Net-(U$11-IO3)") (class "Default")
      (node (ref "JP7") (pin "2") (pinfunction "2_2") (pintype "passive"))
      (node (ref "U$11") (pin "P4") (pinfunction "IO3_P4") (pintype "bidirectional"))
      (node (ref "U$5") (pin "1") (pinfunction "P1_1") (pintype "bidirectional"))
      (node (ref "U$5") (pin "4") (pinfunction "P4_4") (pintype "bidirectional"))
    )
    (net (code "39") (name "Net-(U$11-IO4)") (class "Default")
      (node (ref "JP7") (pin "1") (pinfunction "1_1") (pintype "passive"))
      (node (ref "U$11") (pin "P6") (pinfunction "IO4_P6") (pintype "bidirectional"))
      (node (ref "U$2") (pin "1") (pinfunction "P1_1") (pintype "bidirectional"))
      (node (ref "U$2") (pin "4") (pinfunction "P4_4") (pintype "bidirectional"))
    )
    (net (code "40") (name "Net-(U1-IN+)") (class "Default")
      (node (ref "C9") (pin "1") (pinfunction "1_1") (pintype "passive"))
      (node (ref "R16") (pin "1") (pinfunction "1_1") (pintype "passive"))
      (node (ref "R25") (pin "2") (pinfunction "2_2") (pintype "passive"))
      (node (ref "U1") (pin "3") (pinfunction "IN+_3") (pintype "bidirectional"))
    )
    (net (code "41") (name "Net-(U1-IN-)") (class "Default")
      (node (ref "C8") (pin "2") (pinfunction "2_2") (pintype "passive"))
      (node (ref "R14") (pin "1") (pinfunction "1_1") (pintype "passive"))
      (node (ref "U1") (pin "4") (pinfunction "IN-_4") (pintype "bidirectional"))
    )
    (net (code "42") (name "Net-(U1-OUT)") (class "Default")
      (node (ref "C8") (pin "1") (pinfunction "1_1") (pintype "passive"))
      (node (ref "R15") (pin "1") (pinfunction "1_1") (pintype "passive"))
      (node (ref "U1") (pin "1") (pinfunction "OUT_1") (pintype "bidirectional"))
    )
    (net (code "43") (name "SCK") (class "Default")
      (node (ref "JP1") (pin "9") (pinfunction "9_9") (pintype "passive"))
      (node (ref "U$1") (pin "P15") (pinfunction "PA5_P15") (pintype "bidirectional"))
    )
    (net (code "44") (name "SCL") (class "Default")
      (node (ref "JP1") (pin "12") (pinfunction "12_12") (pintype "passive"))
      (node (ref "U$1") (pin "P6") (pinfunction "PF1_P6") (pintype "bidirectional"))
    )
    (net (code "45") (name "SDA") (class "Default")
      (node (ref "JP1") (pin "10") (pinfunction "10_10") (pintype "passive"))
      (node (ref "U$1") (pin "P5") (pinfunction "PF0_P5") (pintype "bidirectional"))
    )
    (net (code "46") (name "SPI_CS") (class "Default")
      (node (ref "JP1") (pin "7") (pinfunction "7_7") (pintype "passive"))
      (node (ref "U$1") (pin "P18") (pinfunction "PB0_P18") (pintype "bidirectional"))
    )
    (net (code "47") (name "SWCLK") (class "Default")
      (node (ref "JP2") (pin "1") (pinfunction "1_1") (pintype "passive"))
      (node (ref "U$1") (pin "P37") (pinfunction "PA14_P37") (pintype "bidirectional"))
    )
    (net (code "48") (name "SWDIO") (class "Default")
      (node (ref "JP2") (pin "3") (pinfunction "3_3") (pintype "passive"))
      (node (ref "U$1") (pin "P34") (pinfunction "PA13_P34") (pintype "bidirectional"))
    )
    (net (code "49") (name "USB_DM") (class "Default")
      (node (ref "U$1") (pin "P32") (pinfunction "PA11_P32") (pintype "bidirectional"))
      (node (ref "U$12") (pin "P1") (pinfunction "IO1_P1") (pintype "bidirectional"))
      (node (ref "U$3") (pin "P2") (pinfunction "DM_P2") (pintype "bidirectional"))
    )
    (net (code "50") (name "USB_DP") (class "Default")
      (node (ref "U$1") (pin "P33") (pinfunction "PA12_P33") (pintype "bidirectional"))
      (node (ref "U$12") (pin "P3") (pinfunction "IO2_P3") (pintype "bidirectional"))
      (node (ref "U$3") (pin "P3") (pinfunction "DP_P3") (pintype "bidirectional"))
    )
    (net (code "51") (name "VUSB") (class "Default")
      (node (ref "C16") (pin "1") (pinfunction "1_1") (pintype "passive"))
      (node (ref "C22") (pin "1") (pinfunction "1_1") (pintype "passive"))
      (node (ref "C23") (pin "1") (pinfunction "1_1") (pintype "passive"))
      (node (ref "C24") (pin "1") (pinfunction "1_1") (pintype "passive"))
      (node (ref "C25") (pin "1") (pinfunction "1_1") (pintype "passive"))
      (node (ref "D2") (pin "2") (pinfunction "2_2") (pintype "bidirectional"))
      (node (ref "JP1") (pin "5") (pinfunction "5_5") (pintype "passive"))
      (node (ref "L1") (pin "1") (pinfunction "1_1") (pintype "passive"))
      (node (ref "R19") (pin "1") (pinfunction "1_1") (pintype "passive"))
      (node (ref "U$10") (pin "CATHODE") (pinfunction "CATHODE_CATHODE") (pintype "bidirectional"))
      (node (ref "U$11") (pin "P5") (pinfunction "VCC_P5") (pintype "power_in"))
      (node (ref "U$12") (pin "P5") (pinfunction "VCC_P5") (pintype "power_in"))
      (node (ref "U$13") (pin "CATHODE") (pinfunction "CATHODE_CATHODE") (pintype "bidirectional"))
      (node (ref "U$14") (pin "P$1") (pinfunction "P$1_P$1") (pintype "bidirectional"))
      (node (ref "U$2") (pin "2") (pinfunction "P2_2") (pintype "power_in"))
      (node (ref "U$4") (pin "2") (pinfunction "P2_2") (pintype "power_in"))
      (node (ref "U$5") (pin "2") (pinfunction "P2_2") (pintype "power_in"))
      (node (ref "U$6") (pin "2") (pinfunction "P2_2") (pintype "power_in"))
      (node (ref "U$8") (pin "5") (pinfunction "VIN_5") (pintype "bidirectional"))
    )
    (net (code "52") (name "XBARDUAL_OUT") (class "Default")
      (node (ref "C6") (pin "1") (pinfunction "1_1") (pintype "passive"))
      (node (ref "R10") (pin "2") (pinfunction "2_2") (pintype "passive"))
      (node (ref "R27") (pin "1") (pinfunction "1_1") (pintype "passive"))
      (node (ref "R28") (pin "2") (pinfunction "2_2") (pintype "passive"))
      (node (ref "R9") (pin "2") (pinfunction "2_2") (pintype "passive"))
      (node (ref "U$5") (pin "3") (pinfunction "P3_3") (pintype "bidirectional"))
    )
    (net (code "53") (name "XCOARSE_IN") (class "Default")
      (node (ref "IC3") (pin "5") (pinfunction "I_5") (pintype "input"))
      (node (ref "R5") (pin "1") (pinfunction "1_1") (pintype "passive"))
      (node (ref "U$1") (pin "P38") (pinfunction "PA15_P38") (pintype "bidirectional"))
    )
    (net (code "54") (name "XDUAL_OUT") (class "Default")
      (node (ref "C4") (pin "1") (pinfunction "1_1") (pintype "passive"))
      (node (ref "R22") (pin "1") (pinfunction "1_1") (pintype "passive"))
      (node (ref "R23") (pin "2") (pinfunction "2_2") (pintype "passive"))
      (node (ref "R5") (pin "2") (pinfunction "2_2") (pintype "passive"))
      (node (ref "R6") (pin "2") (pinfunction "2_2") (pintype "passive"))
      (node (ref "U$2") (pin "3") (pinfunction "P3_3") (pintype "bidirectional"))
    )
    (net (code "55") (name "XFINE_IN") (class "Default")
      (node (ref "IC3") (pin "9") (pinfunction "I_9") (pintype "input"))
      (node (ref "R6") (pin "1") (pinfunction "1_1") (pintype "passive"))
      (node (ref "U$1") (pin "P39") (pinfunction "PB3_P39") (pintype "bidirectional"))
    )
    (net (code "56") (name "YBARDUAL_OUT") (class "Default")
      (node (ref "C7") (pin "1") (pinfunction "1_1") (pintype "passive"))
      (node (ref "R11") (pin "2") (pinfunction "2_2") (pintype "passive"))
      (node (ref "R12") (pin "2") (pinfunction "2_2") (pintype "passive"))
      (node (ref "R29") (pin "1") (pinfunction "1_1") (pintype "passive"))
      (node (ref "R30") (pin "2") (pinfunction "2_2") (pintype "passive"))
      (node (ref "U$6") (pin "3") (pinfunction "P3_3") (pintype "bidirectional"))
    )
    (net (code "57") (name "YCOARSE_IN") (class "Default")
      (node (ref "IC3") (pin "11") (pinfunction "I_11") (pintype "input"))
      (node (ref "R7") (pin "1") (pinfunction "1_1") (pintype "passive"))
      (node (ref "U$1") (pin "P21") (pinfunction "PB10_P21") (pintype "bidirectional"))
    )
    (net (code "58") (name "YDUAL_OUT") (class "Default")
      (node (ref "C5") (pin "1") (pinfunction "1_1") (pintype "passive"))
      (node (ref "R24") (pin "1") (pinfunction "1_1") (pintype "passive"))
      (node (ref "R26") (pin "2") (pinfunction "2_2") (pintype "passive"))
      (node (ref "R7") (pin "2") (pinfunction "2_2") (pintype "passive"))
      (node (ref "R8") (pin "2") (pinfunction "2_2") (pintype "passive"))
      (node (ref "U$4") (pin "3") (pinfunction "P3_3") (pintype "bidirectional"))
    )
    (net (code "59") (name "YFINE_IN") (class "Default")
      (node (ref "IC3") (pin "13") (pinfunction "I_13") (pintype "input"))
      (node (ref "R8") (pin "1") (pinfunction "1_1") (pintype "passive"))
      (node (ref "U$1") (pin "P22") (pinfunction "PB11_P22") (pintype "bidirectional"))
    )
    (net (code "60") (name "unconnected-(IC3A-O-Pad2)") (class "Default")
      (node (ref "IC3") (pin "2") (pinfunction "O_2") (pintype "output"))
    )
    (net (code "61") (name "unconnected-(IC3B-O-Pad4)") (class "Default")
      (node (ref "IC3") (pin "4") (pinfunction "O_4") (pintype "output"))
    )
    (net (code "62") (name "unconnected-(U$1-PA4-PadP14)") (class "Default")
      (node (ref "U$1") (pin "P14") (pinfunction "PA4_P14") (pintype "bidirectional"))
    )
    (net (code "63") (name "unconnected-(U$1-PA8-PadP29)") (class "Default")
      (node (ref "U$1") (pin "P29") (pinfunction "PA8_P29") (pintype "bidirectional"))
    )
    (net (code "64") (name "unconnected-(U$1-PA9-PadP30)") (class "Default")
      (node (ref "U$1") (pin "P30") (pinfunction "PA9_P30") (pintype "bidirectional"))
    )
    (net (code "65") (name "unconnected-(U$1-PA10-PadP31)") (class "Default")
      (node (ref "U$1") (pin "P31") (pinfunction "PA10_P31") (pintype "bidirectional"))
    )
    (net (code "66") (name "unconnected-(U$1-PB1-PadP19)") (class "Default")
      (node (ref "U$1") (pin "P19") (pinfunction "PB1_P19") (pintype "bidirectional"))
    )
    (net (code "67") (name "unconnected-(U$1-PB2-PadP20)") (class "Default")
      (node (ref "U$1") (pin "P20") (pinfunction "PB2_P20") (pintype "bidirectional"))
    )
    (net (code "68") (name "unconnected-(U$1-PB5-PadP41)") (class "Default")
      (node (ref "U$1") (pin "P41") (pinfunction "PB5_P41") (pintype "bidirectional"))
    )
    (net (code "69") (name "unconnected-(U$1-PB6-PadP42)") (class "Default")
      (node (ref "U$1") (pin "P42") (pinfunction "PB6_P42") (pintype "bidirectional"))
    )
    (net (code "70") (name "unconnected-(U$1-PB7-PadP43)") (class "Default")
      (node (ref "U$1") (pin "P43") (pinfunction "PB7_P43") (pintype "bidirectional"))
    )
    (net (code "71") (name "unconnected-(U$1-PB8-PadP45)") (class "Default")
      (node (ref "U$1") (pin "P45") (pinfunction "PB8_P45") (pintype "bidirectional"))
    )
    (net (code "72") (name "unconnected-(U$1-PB9-PadP46)") (class "Default")
      (node (ref "U$1") (pin "P46") (pinfunction "PB9_P46") (pintype "bidirectional"))
    )
    (net (code "73") (name "unconnected-(U$1-PC13-PadP2)") (class "Default")
      (node (ref "U$1") (pin "P2") (pinfunction "PC13_P2") (pintype "bidirectional"))
    )
    (net (code "74") (name "unconnected-(U$1-PC14-PadP3)") (class "Default")
      (node (ref "U$1") (pin "P3") (pinfunction "PC14_P3") (pintype "bidirectional"))
    )
    (net (code "75") (name "unconnected-(U$1-PC15-PadP4)") (class "Default")
      (node (ref "U$1") (pin "P4") (pinfunction "PC15_P4") (pintype "bidirectional"))
    )
    (net (code "76") (name "unconnected-(U$12-IO3-PadP4)") (class "Default")
      (node (ref "U$12") (pin "P4") (pinfunction "IO3_P4") (pintype "bidirectional"))
    )
    (net (code "77") (name "unconnected-(U$12-IO4-PadP6)") (class "Default")
      (node (ref "U$12") (pin "P6") (pinfunction "IO4_P6") (pintype "bidirectional"))
    )
  )
)
